# motherboard.net
KiCad netlist of a schematic drawn in EAGLE
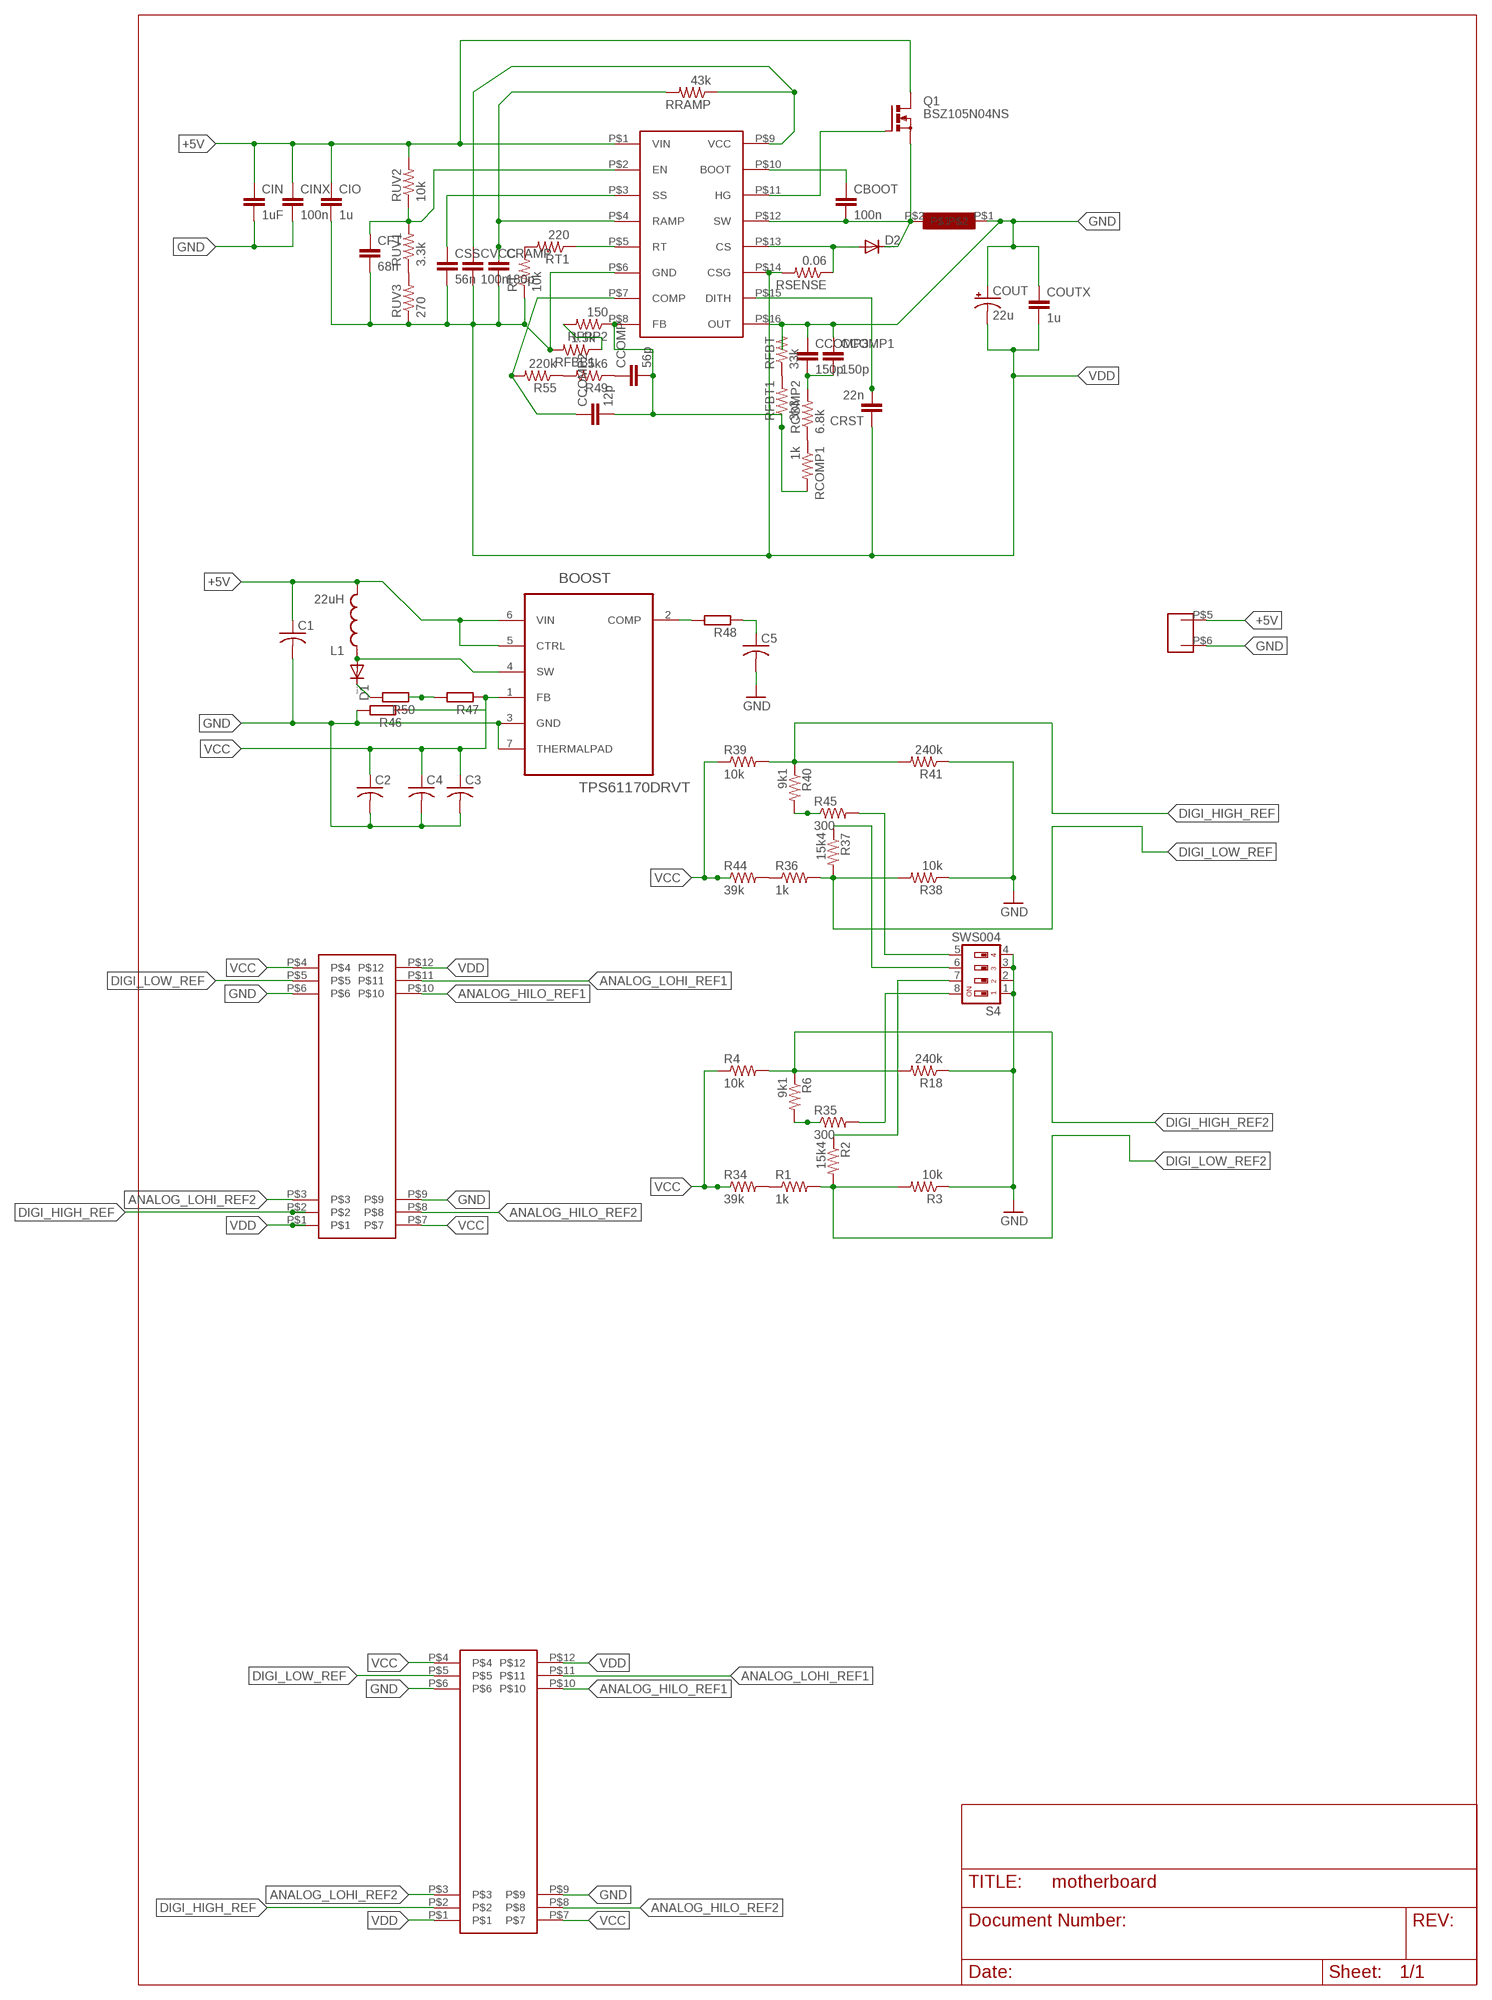
[diagram p0: schematic, sheet 1]

(export (version "E")
  (design (tool "Eeschema 10.0.6"))
  (components
    (comp (ref "BOOST")
      (value "TPS61170DRVT")
      (footprint "eagle-import:SON65P210X210X80-7N")
      (libsource (lib "eagle-import") (part "TPS61170DRVT"))
    )
    (comp (ref "C1")
      (value "C-USC1206")
      (footprint "eagle-import:C1206")
      (libsource (lib "eagle-import") (part "C-USC1206"))
    )
    (comp (ref "C2")
      (value "C-USC0805")
      (footprint "eagle-import:C0805")
      (libsource (lib "eagle-import") (part "C-USC0805"))
    )
    (comp (ref "C3")
      (value "C-USC1206")
      (footprint "eagle-import:C1206")
      (libsource (lib "eagle-import") (part "C-USC1206"))
    )
    (comp (ref "C4")
      (value "C-USC1206")
      (footprint "eagle-import:C1206")
      (libsource (lib "eagle-import") (part "C-USC1206"))
    )
    (comp (ref "C5")
      (value "C-USC1206")
      (footprint "eagle-import:C1206")
      (libsource (lib "eagle-import") (part "C-USC1206"))
    )
    (comp (ref "CBOOT")
      (value "100n")
      (footprint "eagle-import:C0805")
      (libsource (lib "eagle-import") (part "C-EUC0805"))
    )
    (comp (ref "CCOMP")
      (value "56p")
      (footprint "eagle-import:C0805")
      (libsource (lib "eagle-import") (part "C-EUC0805"))
    )
    (comp (ref "CCOMP1")
      (value "150p")
      (footprint "eagle-import:C0805")
      (libsource (lib "eagle-import") (part "C-EUC0805"))
    )
    (comp (ref "CCOMP2")
      (value "12p")
      (footprint "eagle-import:C0805")
      (libsource (lib "eagle-import") (part "C-EUC0805"))
    )
    (comp (ref "CCOMP3")
      (value "150p")
      (footprint "eagle-import:C0805")
      (libsource (lib "eagle-import") (part "C-EUC0805"))
    )
    (comp (ref "CFT")
      (value "68n")
      (footprint "eagle-import:C0805")
      (libsource (lib "eagle-import") (part "C-EUC0805"))
    )
    (comp (ref "CIN")
      (value "1uF")
      (footprint "eagle-import:C0805")
      (libsource (lib "eagle-import") (part "C-EUC0805"))
    )
    (comp (ref "CINX")
      (value "100n")
      (footprint "eagle-import:C0805")
      (libsource (lib "eagle-import") (part "C-EUC0805"))
    )
    (comp (ref "CIO")
      (value "1u")
      (footprint "eagle-import:C0805")
      (libsource (lib "eagle-import") (part "C-EUC0805"))
    )
    (comp (ref "COUT")
      (value "22u")
      (footprint "eagle-import:E5-5")
      (libsource (lib "eagle-import") (part "CPOL-USE5-5"))
    )
    (comp (ref "COUTX")
      (value "1u")
      (footprint "eagle-import:C0805")
      (libsource (lib "eagle-import") (part "C-EUC0805"))
    )
    (comp (ref "CRAMP")
      (value "180p")
      (footprint "eagle-import:C0805")
      (libsource (lib "eagle-import") (part "C-EUC0805"))
    )
    (comp (ref "CRST")
      (value "22n")
      (footprint "eagle-import:C0805")
      (libsource (lib "eagle-import") (part "C-EUC0805"))
    )
    (comp (ref "CSS")
      (value "56n")
      (footprint "eagle-import:C0805")
      (libsource (lib "eagle-import") (part "C-EUC0805"))
    )
    (comp (ref "CVCC")
      (value "100n")
      (footprint "eagle-import:C0805")
      (libsource (lib "eagle-import") (part "C-EUC0805"))
    )
    (comp (ref "D1")
      (value "DIODE-SOD123")
      (footprint "eagle-import:SOD123")
      (libsource (lib "eagle-import") (part "DIODE-SOD123"))
    )
    (comp (ref "D2")
      (value "DIODE-SOD123")
      (footprint "eagle-import:SOD123")
      (libsource (lib "eagle-import") (part "DIODE-SOD123"))
    )
    (comp (ref "L1")
      (value "22uH")
      (footprint "eagle-import:SRN6045")
      (libsource (lib "eagle-import") (part "INDUCTORBOURNS_SRN6045"))
    )
    (comp (ref "Q1")
      (value "BSZ105N04NS")
      (footprint "eagle-import:PG-TDSON-8")
      (libsource (lib "eagle-import") (part "BSZ105N04NS"))
    )
    (comp (ref "R1")
      (value "1k")
      (footprint "eagle-import:R0805")
      (libsource (lib "eagle-import") (part "R-US_R0805"))
    )
    (comp (ref "R2")
      (value "15k4")
      (footprint "eagle-import:R0805")
      (libsource (lib "eagle-import") (part "R-US_R0805"))
    )
    (comp (ref "R3")
      (value "10k")
      (footprint "eagle-import:R0805")
      (libsource (lib "eagle-import") (part "R-US_R0805"))
    )
    (comp (ref "R4")
      (value "10k")
      (footprint "eagle-import:R0805")
      (libsource (lib "eagle-import") (part "R-US_R0805"))
    )
    (comp (ref "R6")
      (value "9k1")
      (footprint "eagle-import:R0805")
      (libsource (lib "eagle-import") (part "R-US_R0805"))
    )
    (comp (ref "R18")
      (value "240k")
      (footprint "eagle-import:R0805")
      (libsource (lib "eagle-import") (part "R-US_R0805"))
    )
    (comp (ref "R34")
      (value "39k")
      (footprint "eagle-import:R0805")
      (libsource (lib "eagle-import") (part "R-US_R0805"))
    )
    (comp (ref "R35")
      (value "300")
      (footprint "eagle-import:R0805")
      (libsource (lib "eagle-import") (part "R-US_R0805"))
    )
    (comp (ref "R36")
      (value "1k")
      (footprint "eagle-import:R0805")
      (libsource (lib "eagle-import") (part "R-US_R0805"))
    )
    (comp (ref "R37")
      (value "15k4")
      (footprint "eagle-import:R0805")
      (libsource (lib "eagle-import") (part "R-US_R0805"))
    )
    (comp (ref "R38")
      (value "10k")
      (footprint "eagle-import:R0805")
      (libsource (lib "eagle-import") (part "R-US_R0805"))
    )
    (comp (ref "R39")
      (value "10k")
      (footprint "eagle-import:R0805")
      (libsource (lib "eagle-import") (part "R-US_R0805"))
    )
    (comp (ref "R40")
      (value "9k1")
      (footprint "eagle-import:R0805")
      (libsource (lib "eagle-import") (part "R-US_R0805"))
    )
    (comp (ref "R41")
      (value "240k")
      (footprint "eagle-import:R0805")
      (libsource (lib "eagle-import") (part "R-US_R0805"))
    )
    (comp (ref "R44")
      (value "39k")
      (footprint "eagle-import:R0805")
      (libsource (lib "eagle-import") (part "R-US_R0805"))
    )
    (comp (ref "R45")
      (value "300")
      (footprint "eagle-import:R0805")
      (libsource (lib "eagle-import") (part "R-US_R0805"))
    )
    (comp (ref "R46")
      (value "R-EU_R0805")
      (footprint "eagle-import:R0805")
      (libsource (lib "eagle-import") (part "R-EU_R0805"))
    )
    (comp (ref "R47")
      (value "R-EU_R0805")
      (footprint "eagle-import:R0805")
      (libsource (lib "eagle-import") (part "R-EU_R0805"))
    )
    (comp (ref "R48")
      (value "R-EU_R0805")
      (footprint "eagle-import:R0805")
      (libsource (lib "eagle-import") (part "R-EU_R0805"))
    )
    (comp (ref "R49")
      (value "5k6")
      (footprint "eagle-import:R0805")
      (libsource (lib "eagle-import") (part "R-US_R0805"))
    )
    (comp (ref "R50")
      (value "R-EU_R0805")
      (footprint "eagle-import:R0805")
      (libsource (lib "eagle-import") (part "R-EU_R0805"))
    )
    (comp (ref "R55")
      (value "220k")
      (footprint "eagle-import:R0805")
      (libsource (lib "eagle-import") (part "R-US_R0805"))
    )
    (comp (ref "RCOMP1")
      (value "1k")
      (footprint "eagle-import:R0805")
      (libsource (lib "eagle-import") (part "R-US_R0805"))
    )
    (comp (ref "RCOMP2")
      (value "6.8k")
      (footprint "eagle-import:R0805")
      (libsource (lib "eagle-import") (part "R-US_R0805"))
    )
    (comp (ref "RFBB1")
      (value "1.5k")
      (footprint "eagle-import:R0805")
      (libsource (lib "eagle-import") (part "R-US_R0805"))
    )
    (comp (ref "RFBT")
      (value "33k")
      (footprint "eagle-import:R0805")
      (libsource (lib "eagle-import") (part "R-US_R0805"))
    )
    (comp (ref "RFBT1")
      (value "3k3")
      (footprint "eagle-import:R0805")
      (libsource (lib "eagle-import") (part "R-US_R0805"))
    )
    (comp (ref "RFPP2")
      (value "150")
      (footprint "eagle-import:R0805")
      (libsource (lib "eagle-import") (part "R-US_R0805"))
    )
    (comp (ref "RRAMP")
      (value "43k")
      (footprint "eagle-import:R0805")
      (libsource (lib "eagle-import") (part "R-US_R0805"))
    )
    (comp (ref "RSENSE")
      (value "0.06")
      (footprint "eagle-import:R0805")
      (libsource (lib "eagle-import") (part "R-US_R0805"))
    )
    (comp (ref "RT")
      (value "10k")
      (footprint "eagle-import:R0805")
      (libsource (lib "eagle-import") (part "R-US_R0805"))
    )
    (comp (ref "RT1")
      (value "220")
      (footprint "eagle-import:R0805")
      (libsource (lib "eagle-import") (part "R-US_R0805"))
    )
    (comp (ref "RUV1")
      (value "3.3k")
      (footprint "eagle-import:R0805")
      (libsource (lib "eagle-import") (part "R-US_R0805"))
    )
    (comp (ref "RUV2")
      (value "10k")
      (footprint "eagle-import:R0805")
      (libsource (lib "eagle-import") (part "R-US_R0805"))
    )
    (comp (ref "RUV3")
      (value "270")
      (footprint "eagle-import:R0805")
      (libsource (lib "eagle-import") (part "R-US_R0805"))
    )
    (comp (ref "S4")
      (value "SWS004")
      (footprint "eagle-import:SMS-004")
      (libsource (lib "eagle-import") (part "SWS004"))
    )
    (comp (ref "U$1")
      (value "MODULE_CONNECTOR")
      (footprint "eagle-import:MODULE_CONNECTOR")
      (libsource (lib "eagle-import") (part "MODULE_CONNECTOR"))
    )
    (comp (ref "U$2")
      (value "LM5088")
      (footprint "eagle-import:LM5088")
      (libsource (lib "eagle-import") (part "LM5088"))
    )
    (comp (ref "U$3")
      (value "KLICK_INDUCTOR01")
      (footprint "eagle-import:KLICK_INDUCTOR01")
      (libsource (lib "eagle-import") (part "KLICK_INDUCTOR01"))
    )
    (comp (ref "U$4")
      (value "5.08PITCHTERMINAL")
      (footprint "eagle-import:10KPL508")
      (libsource (lib "eagle-import") (part "5.08PITCHTERMINAL"))
    )
    (comp (ref "U$5")
      (value "MODULE_CONNECTOR")
      (footprint "eagle-import:MODULE_CONNECTOR")
      (libsource (lib "eagle-import") (part "MODULE_CONNECTOR"))
    )
  )
  (nets
    (net (code "1") (name "+5V") (class "Default")
      (node (ref "BOOST") (pin "5") (pinfunction "CTRL_5") (pintype "input"))
      (node (ref "BOOST") (pin "6") (pinfunction "VIN_6") (pintype "power_in"))
      (node (ref "C1") (pin "1") (pinfunction "1_1") (pintype "passive"))
      (node (ref "CIN") (pin "1") (pinfunction "1_1") (pintype "passive"))
      (node (ref "CINX") (pin "1") (pinfunction "1_1") (pintype "passive"))
      (node (ref "CIO") (pin "1") (pinfunction "1_1") (pintype "passive"))
      (node (ref "L1") (pin "2") (pinfunction "2_2") (pintype "passive"))
      (node (ref "Q1") (pin "5") (pinfunction "D_5") (pintype "passive"))
      (node (ref "Q1") (pin "6") (pinfunction "D_6") (pintype "passive"))
      (node (ref "Q1") (pin "7") (pinfunction "D_7") (pintype "passive"))
      (node (ref "Q1") (pin "8") (pinfunction "D_8") (pintype "passive"))
      (node (ref "Q1") (pin "TH") (pinfunction "D_TH") (pintype "passive"))
      (node (ref "RUV2") (pin "2") (pinfunction "2_2") (pintype "passive"))
      (node (ref "U$2") (pin "P$1") (pinfunction "VIN_P$1") (pintype "bidirectional"))
      (node (ref "U$4") (pin "P$5") (pinfunction "P$5_P$5") (pintype "bidirectional"))
    )
    (net (code "2") (name "ANALOG_HILO_REF1") (class "Default")
      (node (ref "U$1") (pin "P$10") (pinfunction "P$10_P$10") (pintype "bidirectional"))
      (node (ref "U$5") (pin "P$10") (pinfunction "P$10_P$10") (pintype "bidirectional"))
    )
    (net (code "3") (name "ANALOG_HILO_REF2") (class "Default")
      (node (ref "U$1") (pin "P$8") (pinfunction "P$8_P$8") (pintype "bidirectional"))
      (node (ref "U$5") (pin "P$8") (pinfunction "P$8_P$8") (pintype "bidirectional"))
    )
    (net (code "4") (name "ANALOG_LOHI_REF1") (class "Default")
      (node (ref "U$1") (pin "P$11") (pinfunction "P$11_P$11") (pintype "bidirectional"))
      (node (ref "U$5") (pin "P$11") (pinfunction "P$11_P$11") (pintype "bidirectional"))
    )
    (net (code "5") (name "ANALOG_LOHI_REF2") (class "Default")
      (node (ref "U$1") (pin "P$3") (pinfunction "P$3_P$3") (pintype "bidirectional"))
      (node (ref "U$5") (pin "P$3") (pinfunction "P$3_P$3") (pintype "bidirectional"))
    )
    (net (code "6") (name "DIGI_HIGH_REF") (class "Default")
      (node (ref "R39") (pin "2") (pinfunction "2_2") (pintype "passive"))
      (node (ref "R40") (pin "1") (pinfunction "1_1") (pintype "passive"))
      (node (ref "R41") (pin "2") (pinfunction "2_2") (pintype "passive"))
      (node (ref "U$1") (pin "P$2") (pinfunction "P$2_P$2") (pintype "bidirectional"))
      (node (ref "U$5") (pin "P$2") (pinfunction "P$2_P$2") (pintype "bidirectional"))
    )
    (net (code "7") (name "DIGI_HIGH_REF2") (class "Default")
      (node (ref "R18") (pin "2") (pinfunction "2_2") (pintype "passive"))
      (node (ref "R4") (pin "2") (pinfunction "2_2") (pintype "passive"))
      (node (ref "R6") (pin "1") (pinfunction "1_1") (pintype "passive"))
    )
    (net (code "8") (name "DIGI_LOW_REF") (class "Default")
      (node (ref "R36") (pin "2") (pinfunction "2_2") (pintype "passive"))
      (node (ref "R37") (pin "2") (pinfunction "2_2") (pintype "passive"))
      (node (ref "R38") (pin "2") (pinfunction "2_2") (pintype "passive"))
      (node (ref "U$1") (pin "P$5") (pinfunction "P$5_P$5") (pintype "bidirectional"))
      (node (ref "U$5") (pin "P$5") (pinfunction "P$5_P$5") (pintype "bidirectional"))
    )
    (net (code "9") (name "DIGI_LOW_REF2") (class "Default")
      (node (ref "R1") (pin "2") (pinfunction "2_2") (pintype "passive"))
      (node (ref "R2") (pin "2") (pinfunction "2_2") (pintype "passive"))
      (node (ref "R3") (pin "2") (pinfunction "2_2") (pintype "passive"))
    )
    (net (code "10") (name "GND") (class "Default")
      (node (ref "BOOST") (pin "3") (pinfunction "GND_3") (pintype "passive"))
      (node (ref "BOOST") (pin "7") (pinfunction "THERMALPAD_7") (pintype "passive"))
      (node (ref "C1") (pin "2") (pinfunction "2_2") (pintype "passive"))
      (node (ref "C2") (pin "2") (pinfunction "2_2") (pintype "passive"))
      (node (ref "C3") (pin "2") (pinfunction "2_2") (pintype "passive"))
      (node (ref "C4") (pin "2") (pinfunction "2_2") (pintype "passive"))
      (node (ref "C5") (pin "2") (pinfunction "2_2") (pintype "passive"))
      (node (ref "CCOMP1") (pin "1") (pinfunction "1_1") (pintype "passive"))
      (node (ref "CCOMP3") (pin "1") (pinfunction "1_1") (pintype "passive"))
      (node (ref "CIN") (pin "2") (pinfunction "2_2") (pintype "passive"))
      (node (ref "CINX") (pin "2") (pinfunction "2_2") (pintype "passive"))
      (node (ref "COUT") (pin "+") (pinfunction "+_+") (pintype "passive"))
      (node (ref "COUTX") (pin "1") (pinfunction "1_1") (pintype "passive"))
      (node (ref "R18") (pin "1") (pinfunction "1_1") (pintype "passive"))
      (node (ref "R3") (pin "1") (pinfunction "1_1") (pintype "passive"))
      (node (ref "R38") (pin "1") (pinfunction "1_1") (pintype "passive"))
      (node (ref "R41") (pin "1") (pinfunction "1_1") (pintype "passive"))
      (node (ref "R46") (pin "2") (pinfunction "2_2") (pintype "passive"))
      (node (ref "RFBT") (pin "2") (pinfunction "2_2") (pintype "passive"))
      (node (ref "S4") (pin "1") (pinfunction "1_1") (pintype "passive"))
      (node (ref "S4") (pin "2") (pinfunction "2_2") (pintype "passive"))
      (node (ref "S4") (pin "3") (pinfunction "3_3") (pintype "passive"))
      (node (ref "S4") (pin "4") (pinfunction "4_4") (pintype "passive"))
      (node (ref "U$1") (pin "P$6") (pinfunction "P$6_P$6") (pintype "bidirectional"))
      (node (ref "U$1") (pin "P$9") (pinfunction "P$9_P$9") (pintype "bidirectional"))
      (node (ref "U$2") (pin "P$16") (pinfunction "OUT_P$16") (pintype "bidirectional"))
      (node (ref "U$3") (pin "P$1") (pinfunction "P$1_P$1") (pintype "bidirectional"))
      (node (ref "U$4") (pin "P$6") (pinfunction "P$6_P$6") (pintype "bidirectional"))
      (node (ref "U$5") (pin "P$6") (pinfunction "P$6_P$6") (pintype "bidirectional"))
      (node (ref "U$5") (pin "P$9") (pinfunction "P$9_P$9") (pintype "bidirectional"))
    )
    (net (code "11") (name "Net-(BOOST-COMP)") (class "Default")
      (node (ref "BOOST") (pin "2") (pinfunction "COMP_2") (pintype "output"))
      (node (ref "R48") (pin "2") (pinfunction "2_2") (pintype "passive"))
    )
    (net (code "12") (name "Net-(BOOST-SW)") (class "Default")
      (node (ref "BOOST") (pin "4") (pinfunction "SW_4") (pintype "input"))
      (node (ref "D1") (pin "A") (pinfunction "A_A") (pintype "passive"))
      (node (ref "L1") (pin "1") (pinfunction "1_1") (pintype "passive"))
    )
    (net (code "13") (name "Net-(C5-Pad1)") (class "Default")
      (node (ref "C5") (pin "1") (pinfunction "1_1") (pintype "passive"))
      (node (ref "R48") (pin "1") (pinfunction "1_1") (pintype "passive"))
    )
    (net (code "14") (name "Net-(CCOMP-Pad1)") (class "Default")
      (node (ref "CCOMP") (pin "1") (pinfunction "1_1") (pintype "passive"))
      (node (ref "R49") (pin "1") (pinfunction "1_1") (pintype "passive"))
    )
    (net (code "15") (name "Net-(CCOMP1-Pad2)") (class "Default")
      (node (ref "CCOMP1") (pin "2") (pinfunction "2_2") (pintype "passive"))
      (node (ref "CCOMP3") (pin "2") (pinfunction "2_2") (pintype "passive"))
      (node (ref "RCOMP2") (pin "2") (pinfunction "2_2") (pintype "passive"))
    )
    (net (code "16") (name "Net-(D1-PadC)") (class "Default")
      (node (ref "D1") (pin "C") (pinfunction "C_C") (pintype "passive"))
      (node (ref "R50") (pin "2") (pinfunction "2_2") (pintype "passive"))
    )
    (net (code "17") (name "Net-(Q1-G)") (class "Default")
      (node (ref "Q1") (pin "4") (pinfunction "G_4") (pintype "passive"))
      (node (ref "U$2") (pin "P$11") (pinfunction "HG_P$11") (pintype "bidirectional"))
    )
    (net (code "18") (name "Net-(R1-Pad1)") (class "Default")
      (node (ref "R1") (pin "1") (pinfunction "1_1") (pintype "passive"))
      (node (ref "R34") (pin "2") (pinfunction "2_2") (pintype "passive"))
    )
    (net (code "19") (name "Net-(R2-Pad1)") (class "Default")
      (node (ref "R2") (pin "1") (pinfunction "1_1") (pintype "passive"))
      (node (ref "S4") (pin "7") (pinfunction "7_7") (pintype "passive"))
    )
    (net (code "20") (name "Net-(R35-Pad1)") (class "Default")
      (node (ref "R35") (pin "1") (pinfunction "1_1") (pintype "passive"))
      (node (ref "R6") (pin "2") (pinfunction "2_2") (pintype "passive"))
    )
    (net (code "21") (name "Net-(R35-Pad2)") (class "Default")
      (node (ref "R35") (pin "2") (pinfunction "2_2") (pintype "passive"))
      (node (ref "S4") (pin "8") (pinfunction "8_8") (pintype "passive"))
    )
    (net (code "22") (name "Net-(R36-Pad1)") (class "Default")
      (node (ref "R36") (pin "1") (pinfunction "1_1") (pintype "passive"))
      (node (ref "R44") (pin "2") (pinfunction "2_2") (pintype "passive"))
    )
    (net (code "23") (name "Net-(R37-Pad1)") (class "Default")
      (node (ref "R37") (pin "1") (pinfunction "1_1") (pintype "passive"))
      (node (ref "S4") (pin "6") (pinfunction "6_6") (pintype "passive"))
    )
    (net (code "24") (name "Net-(R40-Pad2)") (class "Default")
      (node (ref "R40") (pin "2") (pinfunction "2_2") (pintype "passive"))
      (node (ref "R45") (pin "1") (pinfunction "1_1") (pintype "passive"))
    )
    (net (code "25") (name "Net-(R45-Pad2)") (class "Default")
      (node (ref "R45") (pin "2") (pinfunction "2_2") (pintype "passive"))
      (node (ref "S4") (pin "5") (pinfunction "5_5") (pintype "passive"))
    )
    (net (code "26") (name "Net-(R47-Pad2)") (class "Default")
      (node (ref "R47") (pin "2") (pinfunction "2_2") (pintype "passive"))
      (node (ref "R50") (pin "1") (pinfunction "1_1") (pintype "passive"))
    )
    (net (code "27") (name "Net-(R49-Pad2)") (class "Default")
      (node (ref "R49") (pin "2") (pinfunction "2_2") (pintype "passive"))
      (node (ref "R55") (pin "1") (pinfunction "1_1") (pintype "passive"))
    )
    (net (code "28") (name "Net-(RCOMP1-Pad1)") (class "Default")
      (node (ref "RCOMP1") (pin "1") (pinfunction "1_1") (pintype "passive"))
      (node (ref "RCOMP2") (pin "1") (pinfunction "1_1") (pintype "passive"))
    )
    (net (code "29") (name "Net-(RFBB1-Pad1)") (class "Default")
      (node (ref "RFBB1") (pin "1") (pinfunction "1_1") (pintype "passive"))
      (node (ref "RFPP2") (pin "2") (pinfunction "2_2") (pintype "passive"))
    )
    (net (code "30") (name "Net-(RFBT-Pad1)") (class "Default")
      (node (ref "RFBT") (pin "1") (pinfunction "1_1") (pintype "passive"))
      (node (ref "RFBT1") (pin "2") (pinfunction "2_2") (pintype "passive"))
    )
    (net (code "31") (name "Net-(RT-Pad2)") (class "Default")
      (node (ref "RT") (pin "2") (pinfunction "2_2") (pintype "passive"))
      (node (ref "RT1") (pin "2") (pinfunction "2_2") (pintype "passive"))
    )
    (net (code "32") (name "Net-(RUV1-Pad1)") (class "Default")
      (node (ref "RUV1") (pin "1") (pinfunction "1_1") (pintype "passive"))
      (node (ref "RUV3") (pin "2") (pinfunction "2_2") (pintype "passive"))
    )
    (net (code "33") (name "Net-(U$2-BOOT)") (class "Default")
      (node (ref "CBOOT") (pin "1") (pinfunction "1_1") (pintype "passive"))
      (node (ref "U$2") (pin "P$10") (pinfunction "BOOT_P$10") (pintype "bidirectional"))
    )
    (net (code "34") (name "Net-(U$2-COMP)") (class "Default")
      (node (ref "CCOMP2") (pin "1") (pinfunction "1_1") (pintype "passive"))
      (node (ref "R55") (pin "2") (pinfunction "2_2") (pintype "passive"))
      (node (ref "U$2") (pin "P$7") (pinfunction "COMP_P$7") (pintype "bidirectional"))
    )
    (net (code "35") (name "Net-(U$2-CS)") (class "Default")
      (node (ref "D2") (pin "A") (pinfunction "A_A") (pintype "passive"))
      (node (ref "RSENSE") (pin "1") (pinfunction "1_1") (pintype "passive"))
      (node (ref "U$2") (pin "P$13") (pinfunction "CS_P$13") (pintype "bidirectional"))
    )
    (net (code "36") (name "Net-(U$2-DITH)") (class "Default")
      (node (ref "CRST") (pin "2") (pinfunction "2_2") (pintype "passive"))
      (node (ref "U$2") (pin "P$15") (pinfunction "DITH_P$15") (pintype "bidirectional"))
    )
    (net (code "37") (name "Net-(U$2-EN)") (class "Default")
      (node (ref "CFT") (pin "1") (pinfunction "1_1") (pintype "passive"))
      (node (ref "RUV1") (pin "2") (pinfunction "2_2") (pintype "passive"))
      (node (ref "RUV2") (pin "1") (pinfunction "1_1") (pintype "passive"))
      (node (ref "U$2") (pin "P$2") (pinfunction "EN_P$2") (pintype "bidirectional"))
    )
    (net (code "38") (name "Net-(U$2-FB)") (class "Default")
      (node (ref "CCOMP") (pin "2") (pinfunction "2_2") (pintype "passive"))
      (node (ref "CCOMP2") (pin "2") (pinfunction "2_2") (pintype "passive"))
      (node (ref "RCOMP1") (pin "2") (pinfunction "2_2") (pintype "passive"))
      (node (ref "RFBT1") (pin "1") (pinfunction "1_1") (pintype "passive"))
      (node (ref "RFPP2") (pin "1") (pinfunction "1_1") (pintype "passive"))
      (node (ref "U$2") (pin "P$8") (pinfunction "FB_P$8") (pintype "bidirectional"))
    )
    (net (code "39") (name "Net-(U$2-RAMP)") (class "Default")
      (node (ref "CRAMP") (pin "1") (pinfunction "1_1") (pintype "passive"))
      (node (ref "RRAMP") (pin "2") (pinfunction "2_2") (pintype "passive"))
      (node (ref "U$2") (pin "P$4") (pinfunction "RAMP_P$4") (pintype "bidirectional"))
    )
    (net (code "40") (name "Net-(U$2-RT)") (class "Default")
      (node (ref "RT1") (pin "1") (pinfunction "1_1") (pintype "passive"))
      (node (ref "U$2") (pin "P$5") (pinfunction "RT_P$5") (pintype "bidirectional"))
    )
    (net (code "41") (name "Net-(U$2-SS)") (class "Default")
      (node (ref "CSS") (pin "1") (pinfunction "1_1") (pintype "passive"))
      (node (ref "U$2") (pin "P$3") (pinfunction "SS_P$3") (pintype "bidirectional"))
    )
    (net (code "42") (name "Net-(U$2-SW)") (class "Default")
      (node (ref "CBOOT") (pin "2") (pinfunction "2_2") (pintype "passive"))
      (node (ref "D2") (pin "C") (pinfunction "C_C") (pintype "passive"))
      (node (ref "Q1") (pin "1") (pinfunction "S_1") (pintype "passive"))
      (node (ref "Q1") (pin "2") (pinfunction "S_2") (pintype "passive"))
      (node (ref "Q1") (pin "3") (pinfunction "S_3") (pintype "passive"))
      (node (ref "U$2") (pin "P$12") (pinfunction "SW_P$12") (pintype "bidirectional"))
      (node (ref "U$3") (pin "P$2") (pinfunction "P$2_P$2") (pintype "bidirectional"))
    )
    (net (code "43") (name "Net-(U$2-VCC)") (class "Default")
      (node (ref "CVCC") (pin "1") (pinfunction "1_1") (pintype "passive"))
      (node (ref "RRAMP") (pin "1") (pinfunction "1_1") (pintype "passive"))
      (node (ref "U$2") (pin "P$9") (pinfunction "VCC_P$9") (pintype "bidirectional"))
    )
    (net (code "44") (name "VCC") (class "Default")
      (node (ref "BOOST") (pin "1") (pinfunction "FB_1") (pintype "input"))
      (node (ref "C2") (pin "1") (pinfunction "1_1") (pintype "passive"))
      (node (ref "C3") (pin "1") (pinfunction "1_1") (pintype "passive"))
      (node (ref "C4") (pin "1") (pinfunction "1_1") (pintype "passive"))
      (node (ref "R34") (pin "1") (pinfunction "1_1") (pintype "passive"))
      (node (ref "R39") (pin "1") (pinfunction "1_1") (pintype "passive"))
      (node (ref "R4") (pin "1") (pinfunction "1_1") (pintype "passive"))
      (node (ref "R44") (pin "1") (pinfunction "1_1") (pintype "passive"))
      (node (ref "R46") (pin "1") (pinfunction "1_1") (pintype "passive"))
      (node (ref "R47") (pin "1") (pinfunction "1_1") (pintype "passive"))
      (node (ref "U$1") (pin "P$4") (pinfunction "P$4_P$4") (pintype "bidirectional"))
      (node (ref "U$1") (pin "P$7") (pinfunction "P$7_P$7") (pintype "bidirectional"))
      (node (ref "U$5") (pin "P$4") (pinfunction "P$4_P$4") (pintype "bidirectional"))
      (node (ref "U$5") (pin "P$7") (pinfunction "P$7_P$7") (pintype "bidirectional"))
    )
    (net (code "45") (name "VDD") (class "Default")
      (node (ref "CFT") (pin "2") (pinfunction "2_2") (pintype "passive"))
      (node (ref "CIO") (pin "2") (pinfunction "2_2") (pintype "passive"))
      (node (ref "COUT") (pin "-") (pinfunction "-_-") (pintype "passive"))
      (node (ref "COUTX") (pin "2") (pinfunction "2_2") (pintype "passive"))
      (node (ref "CRAMP") (pin "2") (pinfunction "2_2") (pintype "passive"))
      (node (ref "CRST") (pin "1") (pinfunction "1_1") (pintype "passive"))
      (node (ref "CSS") (pin "2") (pinfunction "2_2") (pintype "passive"))
      (node (ref "CVCC") (pin "2") (pinfunction "2_2") (pintype "passive"))
      (node (ref "RFBB1") (pin "2") (pinfunction "2_2") (pintype "passive"))
      (node (ref "RSENSE") (pin "2") (pinfunction "2_2") (pintype "passive"))
      (node (ref "RT") (pin "1") (pinfunction "1_1") (pintype "passive"))
      (node (ref "RUV3") (pin "1") (pinfunction "1_1") (pintype "passive"))
      (node (ref "U$1") (pin "P$1") (pinfunction "P$1_P$1") (pintype "bidirectional"))
      (node (ref "U$1") (pin "P$12") (pinfunction "P$12_P$12") (pintype "bidirectional"))
      (node (ref "U$2") (pin "P$14") (pinfunction "CSG_P$14") (pintype "bidirectional"))
      (node (ref "U$2") (pin "P$6") (pinfunction "GND_P$6") (pintype "bidirectional"))
      (node (ref "U$5") (pin "P$1") (pinfunction "P$1_P$1") (pintype "bidirectional"))
      (node (ref "U$5") (pin "P$12") (pinfunction "P$12_P$12") (pintype "bidirectional"))
    )
  )
)
